# gas-sensor-mics-6814-mk-1_1.net
KiCad netlist of a schematic drawn in EAGLE
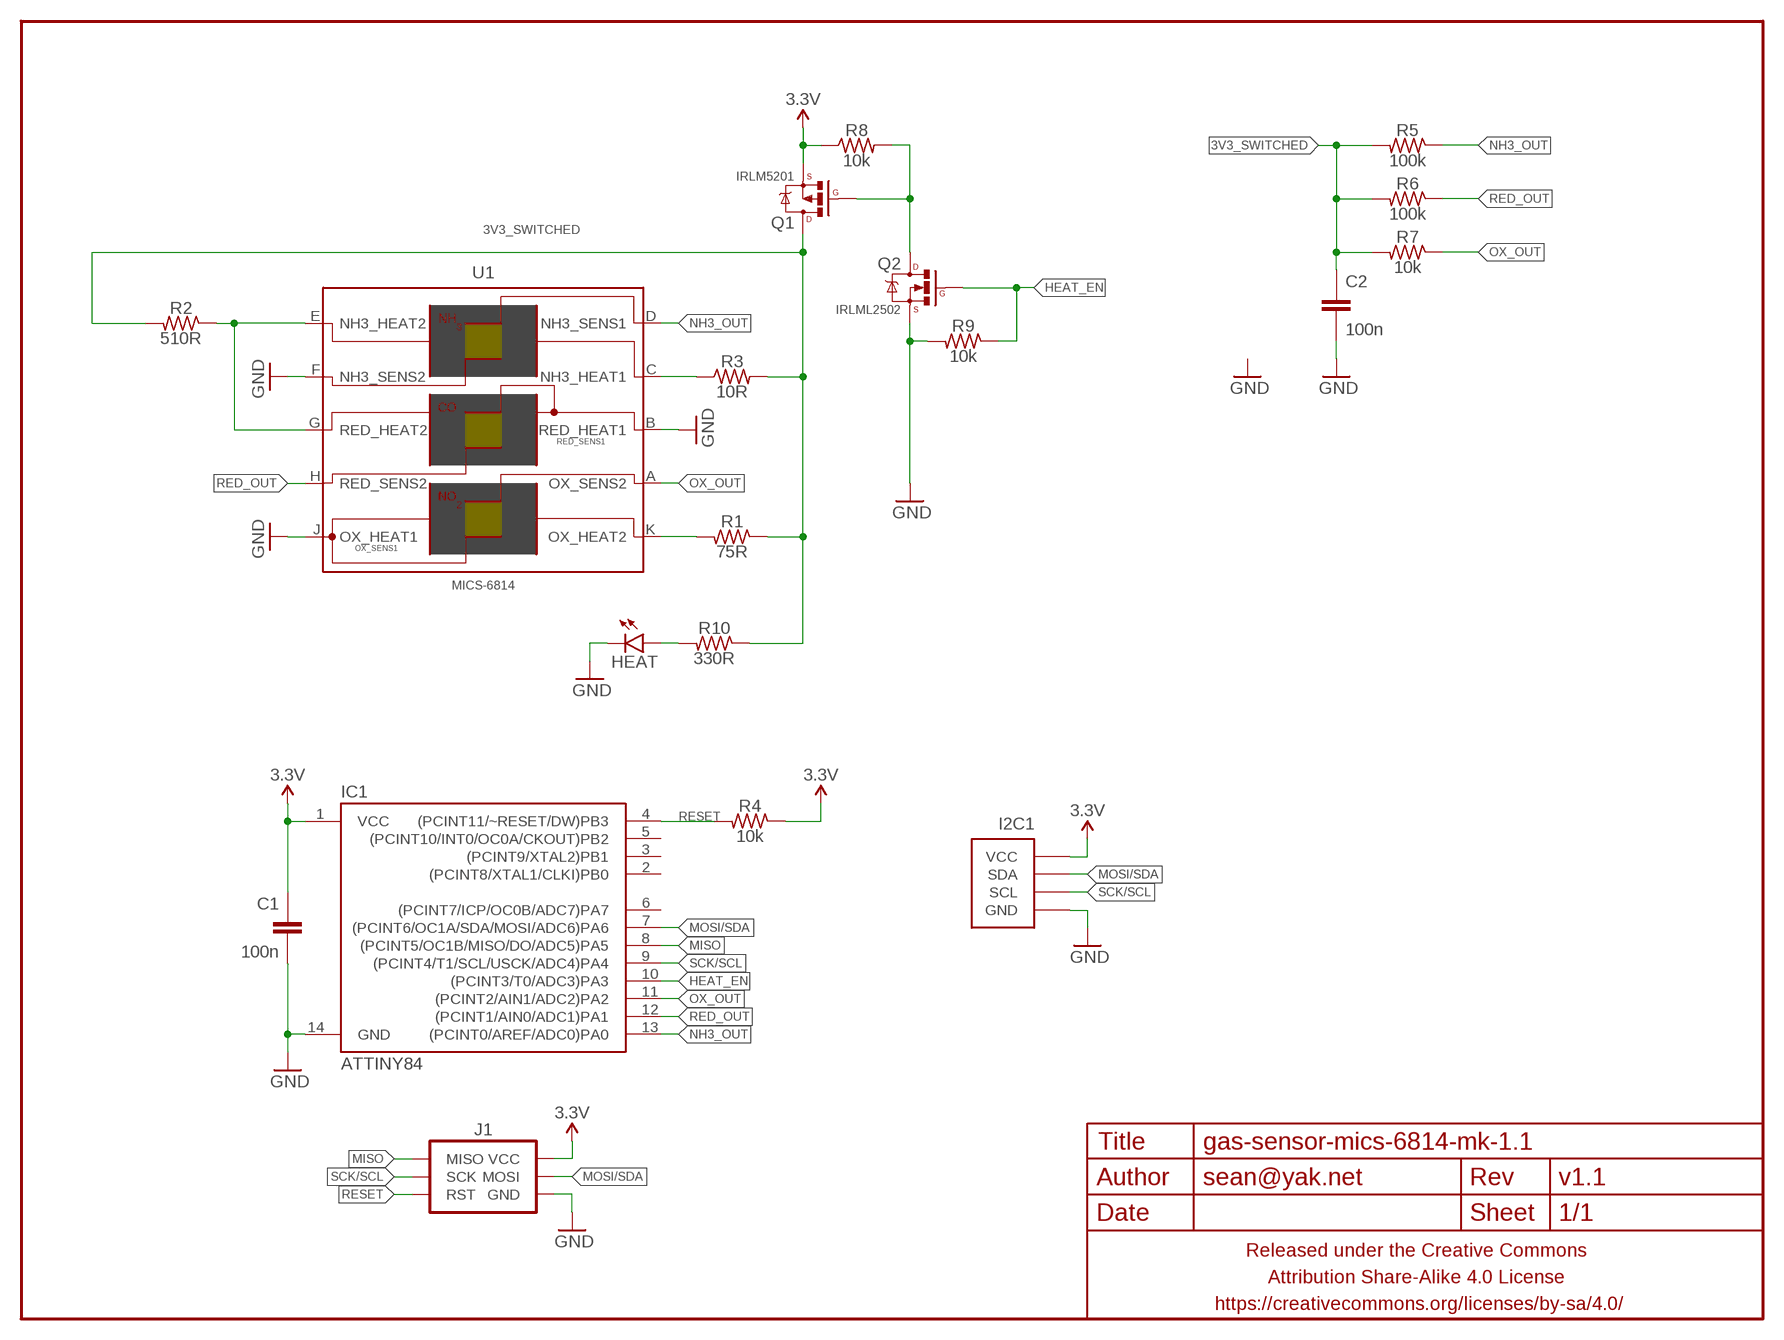
[diagram p0: schematic, sheet 1]

(export (version "E")
  (design (tool "Eeschema 10.0.6"))
  (components
    (comp (ref "C1")
      (value "100n")
      (footprint "eagle-import:C0603-TIGHTER")
      (libsource (lib "eagle-import") (part "CAPACITOR-CERAMICC0603-TIGHTER"))
    )
    (comp (ref "C2")
      (value "100n")
      (footprint "eagle-import:C0603-TIGHTER")
      (libsource (lib "eagle-import") (part "CAPACITOR-CERAMICC0603-TIGHTER"))
    )
    (comp (ref "FRAME1")
      (value "FRAME-LETTERNO_PACKAGE")
      (footprint "eagle-import:DUMMY")
      (fields (field (name "DESIGNER") "sean@yak.net") (field (name "VERSION") "v1.1"))
      (libsource (lib "eagle-import") (part "FRAME-LETTERNO_PACKAGE"))
    )
    (comp (ref "HEAT")
      (value "LED0603-TIGHT")
      (footprint "eagle-import:LED-0603-TIGHT")
      (libsource (lib "eagle-import") (part "LED0603-TIGHT"))
    )
    (comp (ref "I2C1")
      (value "M04-I2CPTH-0.1IN-CENTERED")
      (footprint "eagle-import:1X04-PTH-VERT-I2C-CENTERED")
      (libsource (lib "eagle-import") (part "M04-I2CPTH-0.1IN-CENTERED"))
    )
    (comp (ref "IC1")
      (value "ATTINY84")
      (footprint "eagle-import:SO14")
      (libsource (lib "eagle-import") (part "ATTINY84"))
    )
    (comp (ref "J1")
      (value "AVR_SPI_PRG_6SMD_TEST_POINTS")
      (footprint "eagle-import:2X3_SMD_TEST_POINTS")
      (libsource (lib "eagle-import") (part "AVR_SPI_PRG_6SMD_TEST_POINTS"))
    )
    (comp (ref "Q1")
      (value "IRLM5201")
      (footprint "eagle-import:SOT23")
      (libsource (lib "eagle-import") (part "MOSFET-PCHANNELSOT-23"))
    )
    (comp (ref "Q2")
      (value "IRLML2502")
      (footprint "eagle-import:SOT23")
      (libsource (lib "eagle-import") (part "MOSFET-NCHANNELIRLML2502"))
    )
    (comp (ref "R1")
      (value "75R")
      (footprint "eagle-import:R0603-TIGHTER")
      (libsource (lib "eagle-import") (part "RESISTORR0603-TIGHTER"))
    )
    (comp (ref "R2")
      (value "510R")
      (footprint "eagle-import:R0603-TIGHTER")
      (libsource (lib "eagle-import") (part "RESISTORR0603-TIGHTER"))
    )
    (comp (ref "R3")
      (value "10R")
      (footprint "eagle-import:R0603-TIGHTER")
      (libsource (lib "eagle-import") (part "RESISTORR0603-TIGHTER"))
    )
    (comp (ref "R4")
      (value "10k")
      (footprint "eagle-import:R0603-TIGHTER")
      (libsource (lib "eagle-import") (part "RESISTORR0603-TIGHTER"))
    )
    (comp (ref "R5")
      (value "100k")
      (footprint "eagle-import:R0603-TIGHTER")
      (libsource (lib "eagle-import") (part "RESISTORR0603-TIGHTER"))
    )
    (comp (ref "R6")
      (value "100k")
      (footprint "eagle-import:R0603-TIGHTER")
      (libsource (lib "eagle-import") (part "RESISTORR0603-TIGHTER"))
    )
    (comp (ref "R7")
      (value "10k")
      (footprint "eagle-import:R0603-TIGHTER")
      (libsource (lib "eagle-import") (part "RESISTORR0603-TIGHTER"))
    )
    (comp (ref "R8")
      (value "10k")
      (footprint "eagle-import:R0603-TIGHTER")
      (libsource (lib "eagle-import") (part "RESISTORR0603-TIGHTER"))
    )
    (comp (ref "R9")
      (value "10k")
      (footprint "eagle-import:R0603-TIGHTER")
      (libsource (lib "eagle-import") (part "RESISTORR0603-TIGHTER"))
    )
    (comp (ref "R10")
      (value "330R")
      (footprint "eagle-import:R0603-TIGHTER")
      (libsource (lib "eagle-import") (part "RESISTORR0603-TIGHTER"))
    )
    (comp (ref "U1")
      (value "MICS-6814")
      (footprint "eagle-import:MICS-10-PIN")
      (libsource (lib "eagle-import") (part "MICS-6814"))
    )
  )
  (nets
    (net (code "1") (name "3.3V") (class "Default")
      (node (ref "C1") (pin "1") (pinfunction "1_1") (pintype "passive"))
      (node (ref "I2C1") (pin "VCC") (pinfunction "VCC_VCC") (pintype "bidirectional"))
      (node (ref "IC1") (pin "1") (pinfunction "VCC_1") (pintype "bidirectional"))
      (node (ref "J1") (pin "2") (pinfunction "VCC_2") (pintype "passive"))
      (node (ref "Q1") (pin "2") (pinfunction "S_2") (pintype "passive"))
      (node (ref "R4") (pin "1") (pinfunction "1_1") (pintype "passive"))
      (node (ref "R8") (pin "1") (pinfunction "1_1") (pintype "passive"))
    )
    (net (code "2") (name "3V3_SWITCHED") (class "Default")
      (node (ref "C2") (pin "1") (pinfunction "1_1") (pintype "passive"))
      (node (ref "Q1") (pin "3") (pinfunction "D_3") (pintype "passive"))
      (node (ref "R1") (pin "1") (pinfunction "1_1") (pintype "passive"))
      (node (ref "R10") (pin "1") (pinfunction "1_1") (pintype "passive"))
      (node (ref "R2") (pin "2") (pinfunction "2_2") (pintype "passive"))
      (node (ref "R3") (pin "2") (pinfunction "2_2") (pintype "passive"))
      (node (ref "R5") (pin "2") (pinfunction "2_2") (pintype "passive"))
      (node (ref "R6") (pin "2") (pinfunction "2_2") (pintype "passive"))
      (node (ref "R7") (pin "2") (pinfunction "2_2") (pintype "passive"))
    )
    (net (code "3") (name "GND") (class "Default")
      (node (ref "C1") (pin "2") (pinfunction "2_2") (pintype "passive"))
      (node (ref "C2") (pin "2") (pinfunction "2_2") (pintype "passive"))
      (node (ref "HEAT") (pin "C") (pinfunction "C_C") (pintype "passive"))
      (node (ref "I2C1") (pin "GND") (pinfunction "GND_GND") (pintype "bidirectional"))
      (node (ref "IC1") (pin "14") (pinfunction "GND_14") (pintype "bidirectional"))
      (node (ref "J1") (pin "6") (pinfunction "GND_6") (pintype "passive"))
      (node (ref "Q2") (pin "2") (pinfunction "S_2") (pintype "passive"))
      (node (ref "R9") (pin "2") (pinfunction "2_2") (pintype "passive"))
      (node (ref "U1") (pin "B") (pinfunction "RED_HEAT1_B") (pintype "bidirectional"))
      (node (ref "U1") (pin "F") (pinfunction "NH3_SENS2_F") (pintype "bidirectional"))
      (node (ref "U1") (pin "J") (pinfunction "OX_HEAT1_J") (pintype "bidirectional"))
    )
    (net (code "4") (name "HEAT_EN") (class "Default")
      (node (ref "IC1") (pin "10") (pinfunction "(PCINT3/T0/ADC3)PA3_10") (pintype "bidirectional"))
      (node (ref "Q2") (pin "1") (pinfunction "G_1") (pintype "passive"))
      (node (ref "R9") (pin "1") (pinfunction "1_1") (pintype "passive"))
    )
    (net (code "5") (name "MISO") (class "Default")
      (node (ref "IC1") (pin "8") (pinfunction "(PCINT5/OC1B/MISO/DO/ADC5)PA5_8") (pintype "bidirectional"))
      (node (ref "J1") (pin "1") (pinfunction "MISO_1") (pintype "passive"))
    )
    (net (code "6") (name "MOSI{slash}SDA") (class "Default")
      (node (ref "I2C1") (pin "SDA") (pinfunction "SDA_SDA") (pintype "bidirectional"))
      (node (ref "IC1") (pin "7") (pinfunction "(PCINT6/OC1A/SDA/MOSI/ADC6)PA6_7") (pintype "bidirectional"))
      (node (ref "J1") (pin "4") (pinfunction "MOSI_4") (pintype "passive"))
    )
    (net (code "7") (name "NH3_OUT") (class "Default")
      (node (ref "IC1") (pin "13") (pinfunction "(PCINT0/AREF/ADC0)PA0_13") (pintype "bidirectional"))
      (node (ref "R5") (pin "1") (pinfunction "1_1") (pintype "passive"))
      (node (ref "U1") (pin "D") (pinfunction "NH3_SENS1_D") (pintype "bidirectional"))
    )
    (net (code "8") (name "Net-(HEAT-PadA)") (class "Default")
      (node (ref "HEAT") (pin "A") (pinfunction "A_A") (pintype "passive"))
      (node (ref "R10") (pin "2") (pinfunction "2_2") (pintype "passive"))
    )
    (net (code "9") (name "Net-(Q1-G)") (class "Default")
      (node (ref "Q1") (pin "1") (pinfunction "G_1") (pintype "passive"))
      (node (ref "Q2") (pin "3") (pinfunction "D_3") (pintype "passive"))
      (node (ref "R8") (pin "2") (pinfunction "2_2") (pintype "passive"))
    )
    (net (code "10") (name "Net-(U1-NH3_HEAT1)") (class "Default")
      (node (ref "R3") (pin "1") (pinfunction "1_1") (pintype "passive"))
      (node (ref "U1") (pin "C") (pinfunction "NH3_HEAT1_C") (pintype "bidirectional"))
    )
    (net (code "11") (name "Net-(U1-NH3_HEAT2)") (class "Default")
      (node (ref "R2") (pin "1") (pinfunction "1_1") (pintype "passive"))
      (node (ref "U1") (pin "E") (pinfunction "NH3_HEAT2_E") (pintype "bidirectional"))
      (node (ref "U1") (pin "G") (pinfunction "RED_HEAT2_G") (pintype "bidirectional"))
    )
    (net (code "12") (name "Net-(U1-OX_HEAT2)") (class "Default")
      (node (ref "R1") (pin "2") (pinfunction "2_2") (pintype "passive"))
      (node (ref "U1") (pin "K") (pinfunction "OX_HEAT2_K") (pintype "bidirectional"))
    )
    (net (code "13") (name "OX_OUT") (class "Default")
      (node (ref "IC1") (pin "11") (pinfunction "(PCINT2/AIN1/ADC2)PA2_11") (pintype "bidirectional"))
      (node (ref "R7") (pin "1") (pinfunction "1_1") (pintype "passive"))
      (node (ref "U1") (pin "A") (pinfunction "OX_SENS2_A") (pintype "bidirectional"))
    )
    (net (code "14") (name "RED_OUT") (class "Default")
      (node (ref "IC1") (pin "12") (pinfunction "(PCINT1/AIN0/ADC1)PA1_12") (pintype "bidirectional"))
      (node (ref "R6") (pin "1") (pinfunction "1_1") (pintype "passive"))
      (node (ref "U1") (pin "H") (pinfunction "RED_SENS2_H") (pintype "bidirectional"))
    )
    (net (code "15") (name "RESET") (class "Default")
      (node (ref "IC1") (pin "4") (pinfunction "(PCINT11/~{RESET/DW})PB3_4") (pintype "bidirectional"))
      (node (ref "J1") (pin "5") (pinfunction "RST_5") (pintype "passive"))
      (node (ref "R4") (pin "2") (pinfunction "2_2") (pintype "passive"))
    )
    (net (code "16") (name "SCK{slash}SCL") (class "Default")
      (node (ref "I2C1") (pin "SCL") (pinfunction "SCL_SCL") (pintype "bidirectional"))
      (node (ref "IC1") (pin "9") (pinfunction "(PCINT4/T1/SCL/USCK/ADC4)PA4_9") (pintype "bidirectional"))
      (node (ref "J1") (pin "3") (pinfunction "SCK_3") (pintype "passive"))
    )
    (net (code "17") (name "unconnected-(IC1-(PCINT7{slash}ICP{slash}OC0B{slash}ADC7)PA7-Pad6)") (class "Default")
      (node (ref "IC1") (pin "6") (pinfunction "(PCINT7/ICP/OC0B/ADC7)PA7_6") (pintype "bidirectional"))
    )
    (net (code "18") (name "unconnected-(IC1-(PCINT8{slash}XTAL1{slash}CLKI)PB0-Pad2)") (class "Default")
      (node (ref "IC1") (pin "2") (pinfunction "(PCINT8/XTAL1/CLKI)PB0_2") (pintype "bidirectional"))
    )
    (net (code "19") (name "unconnected-(IC1-(PCINT9{slash}XTAL2)PB1-Pad3)") (class "Default")
      (node (ref "IC1") (pin "3") (pinfunction "(PCINT9/XTAL2)PB1_3") (pintype "bidirectional"))
    )
    (net (code "20") (name "unconnected-(IC1-(PCINT10{slash}INT0{slash}OC0A{slash}CKOUT)PB2-Pad5)") (class "Default")
      (node (ref "IC1") (pin "5") (pinfunction "(PCINT10/INT0/OC0A/CKOUT)PB2_5") (pintype "bidirectional"))
    )
  )
)
